# 08_CAN.net
KiCad netlist of a schematic drawn in Altium Designer
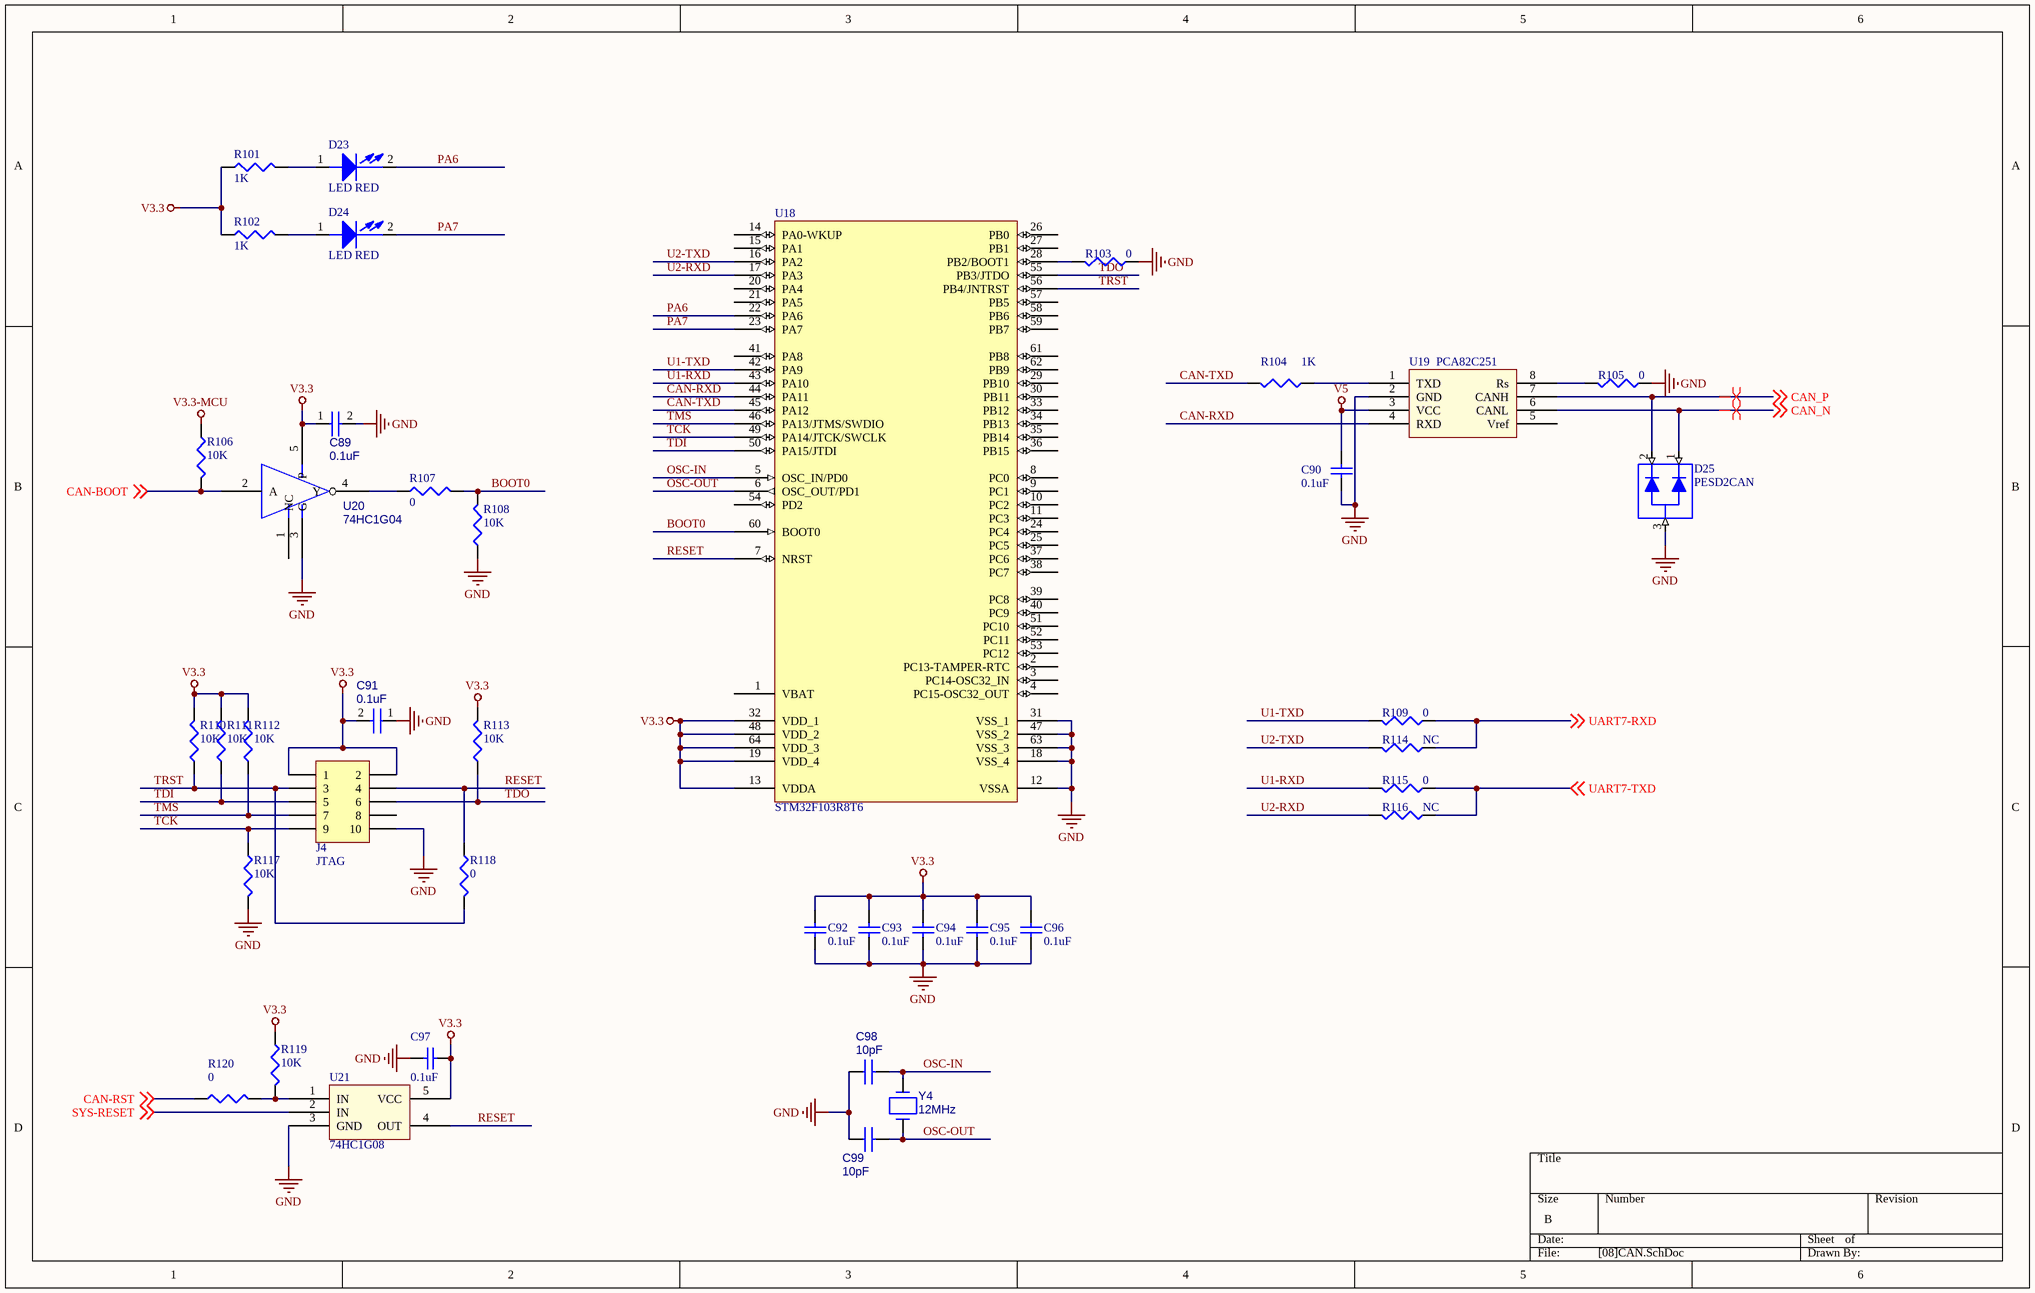
[diagram p0: [08]CAN.SchDoc]

(export (version "E")
  (design (tool "Eeschema 10.0.6"))
  (components
    (comp (ref "C89") (value "0.1uF") (footprint "0603") (libsource (lib "*") (part "CAP NP_Dup2")))
    (comp (ref "C90")
      (value "0.1uF")
      (footprint "0603")
      (description "Capacitor")
      (libsource (lib "Miscellaneous Devices") (part "Cap"))
    )
    (comp (ref "C91") (value "0.1uF") (libsource (lib "*") (part "CAP NP_Dup2")))
    (comp (ref "C92")
      (value "0.1uF")
      (footprint "0603")
      (description "Capacitor")
      (libsource (lib "Miscellaneous Devices") (part "Cap"))
    )
    (comp (ref "C93")
      (value "0.1uF")
      (footprint "0603")
      (description "Capacitor")
      (libsource (lib "Miscellaneous Devices") (part "Cap"))
    )
    (comp (ref "C94")
      (value "0.1uF")
      (footprint "0603")
      (description "Capacitor")
      (libsource (lib "Miscellaneous Devices") (part "Cap"))
    )
    (comp (ref "C95")
      (value "0.1uF")
      (footprint "0603")
      (description "Capacitor")
      (libsource (lib "Miscellaneous Devices") (part "Cap"))
    )
    (comp (ref "C96")
      (value "0.1uF")
      (footprint "0603")
      (description "Capacitor")
      (libsource (lib "Miscellaneous Devices") (part "Cap"))
    )
    (comp (ref "C97")
      (value "0.1uF")
      (footprint "0603")
      (description "Capacitor")
      (libsource (lib "Miscellaneous Devices") (part "Cap"))
    )
    (comp (ref "C98") (value "10pF") (libsource (lib "*") (part "CAP_Dup1")))
    (comp (ref "C99") (value "10pF") (libsource (lib "*") (part "CAP_Dup1")))
    (comp (ref "D23") (value "LED RED") (footprint "LED0603") (libsource (lib "*") (part "LN01401_1")))
    (comp (ref "D24") (value "LED RED") (footprint "LED0603") (libsource (lib "*") (part "LN01401_1")))
    (comp (ref "D25")
      (value "PESD2CAN")
      (footprint "PESD2CAN")
      (fields (field (name "PART NUMBER") "SCA00000J00"))
      (libsource (lib "Schlib") (part "PESD2CAN"))
    )
    (comp (ref "J4")
      (value "JTAG")
      (footprint "HDR2X5")
      (description "Header, 5-Pin, Dual row")
      (libsource (lib "Miscellaneous Connectors") (part "Header 5X2"))
    )
    (comp (ref "R101") (value "1K") (footprint "0603") (libsource (lib "*") (part "CR16-1003FM")))
    (comp (ref "R102") (value "1K") (footprint "0603") (libsource (lib "*") (part "CR16-1003FM")))
    (comp (ref "R103")
      (value "0")
      (footprint "0603")
      (description "Resistor")
      (libsource (lib "Miscellaneous Devices") (part "Res3"))
    )
    (comp (ref "R104")
      (value "1K")
      (footprint "0603")
      (description "Resistor")
      (libsource (lib "Miscellaneous Devices") (part "Res3"))
    )
    (comp (ref "R105")
      (value "0")
      (footprint "0603")
      (description "Resistor")
      (libsource (lib "Miscellaneous Devices") (part "Res3"))
    )
    (comp (ref "R106") (value "10K") (footprint "0603") (libsource (lib "*") (part "CR16-1003FM")))
    (comp (ref "R107")
      (value "0")
      (footprint "0603")
      (description "Resistor")
      (libsource (lib "Miscellaneous Devices") (part "Res3"))
    )
    (comp (ref "R108")
      (value "10K")
      (footprint "0603")
      (description "Resistor")
      (libsource (lib "Miscellaneous Devices") (part "Res3"))
    )
    (comp (ref "R109")
      (value "0")
      (footprint "0603")
      (description "Resistor")
      (libsource (lib "Miscellaneous Devices") (part "Res3"))
    )
    (comp (ref "R110")
      (value "10K")
      (footprint "0603")
      (description "Resistor")
      (libsource (lib "Miscellaneous Devices") (part "Res3"))
    )
    (comp (ref "R111")
      (value "10K")
      (footprint "0603")
      (description "Resistor")
      (libsource (lib "Miscellaneous Devices") (part "Res3"))
    )
    (comp (ref "R112")
      (value "10K")
      (footprint "0603")
      (description "Resistor")
      (libsource (lib "Miscellaneous Devices") (part "Res3"))
    )
    (comp (ref "R113")
      (value "10K")
      (footprint "0603")
      (description "Resistor")
      (libsource (lib "Miscellaneous Devices") (part "Res3"))
    )
    (comp (ref "R114")
      (value "NC")
      (footprint "0603")
      (description "Resistor")
      (libsource (lib "Miscellaneous Devices") (part "Res3"))
    )
    (comp (ref "R115")
      (value "0")
      (footprint "0603")
      (description "Resistor")
      (libsource (lib "Miscellaneous Devices") (part "Res3"))
    )
    (comp (ref "R116")
      (value "NC")
      (footprint "0603")
      (description "Resistor")
      (libsource (lib "Miscellaneous Devices") (part "Res3"))
    )
    (comp (ref "R117")
      (value "10K")
      (footprint "0603")
      (description "Resistor")
      (libsource (lib "Miscellaneous Devices") (part "Res3"))
    )
    (comp (ref "R118")
      (value "0")
      (footprint "0603")
      (description "Resistor")
      (libsource (lib "Miscellaneous Devices") (part "Res3"))
    )
    (comp (ref "R119")
      (value "10K")
      (footprint "0603")
      (description "Resistor")
      (libsource (lib "Miscellaneous Devices") (part "Res3"))
    )
    (comp (ref "R120")
      (value "0")
      (footprint "0603")
      (description "Resistor")
      (libsource (lib "Miscellaneous Devices") (part "Res3"))
    )
    (comp (ref "U18")
      (value "STM32F103R8T6")
      (footprint "LQFP64_N")
      (description "STM32 ARM-based 32-bit MCU with 64 Kbytes Flash, 64-pin LQFP, Industrial Temperature")
      (fields (field (name "PUBLISHER") "Altium Limited"))
      (libsource (lib "ST Microcontroller 32-Bit STM32") (part "STM32F103R8T6"))
    )
    (comp (ref "U19") (value "PCA82C251") (footprint "SO8") (libsource (lib "Schlib") (part "PCA82C251")))
    (comp (ref "U20") (value "74HC1G04") (libsource (lib "*") (part "74LVC1G04GW_SOT353-5")))
    (comp (ref "U21") (value "74HC1G08") (footprint "SOT23-5") (libsource (lib "Schlib") (part "74HC1G08")))
    (comp (ref "Y4") (value "12MHz") (libsource (lib "*") (part "CRYSTAL")))
  )
  (nets
    (net (code "1") (name "/BOOT0") (class "Default")
      (node (ref "R107") (pin "2") (pinfunction "2_2") (pintype "passive"))
      (node (ref "R108") (pin "2") (pinfunction "2_2") (pintype "passive"))
      (node (ref "U18") (pin "60") (pinfunction "BOOT0_60") (pintype "input"))
    )
    (net (code "2") (name "/CAN-RXD") (class "Default")
      (node (ref "U18") (pin "44") (pinfunction "PA11_44") (pintype "bidirectional"))
      (node (ref "U19") (pin "4") (pinfunction "RXD_4") (pintype "passive"))
    )
    (net (code "3") (name "/CAN-TXD") (class "Default")
      (node (ref "R104") (pin "2") (pinfunction "2_2") (pintype "passive"))
      (node (ref "U18") (pin "45") (pinfunction "PA12_45") (pintype "bidirectional"))
    )
    (net (code "4") (name "/OSC-IN") (class "Default")
      (node (ref "C98") (pin "2") (pinfunction "2_2") (pintype "passive"))
      (node (ref "U18") (pin "5") (pinfunction "OSC_IN/PD0_5") (pintype "input"))
      (node (ref "Y4") (pin "2") (pinfunction "2_2") (pintype "passive"))
    )
    (net (code "5") (name "/OSC-OUT") (class "Default")
      (node (ref "C99") (pin "2") (pinfunction "2_2") (pintype "passive"))
      (node (ref "U18") (pin "6") (pinfunction "OSC_OUT/PD1_6") (pintype "output"))
      (node (ref "Y4") (pin "1") (pinfunction "1_1") (pintype "passive"))
    )
    (net (code "6") (name "/PA6") (class "Default")
      (node (ref "D23") (pin "2") (pinfunction "CATHODE_2") (pintype "passive"))
      (node (ref "U18") (pin "22") (pinfunction "PA6_22") (pintype "bidirectional"))
    )
    (net (code "7") (name "/PA7") (class "Default")
      (node (ref "D24") (pin "2") (pinfunction "CATHODE_2") (pintype "passive"))
      (node (ref "U18") (pin "23") (pinfunction "PA7_23") (pintype "bidirectional"))
    )
    (net (code "8") (name "/RESET") (class "Default")
      (node (ref "J4") (pin "4") (pinfunction "4_4") (pintype "passive"))
      (node (ref "R118") (pin "1") (pinfunction "1_1") (pintype "passive"))
      (node (ref "U18") (pin "7") (pinfunction "NRST_7") (pintype "bidirectional"))
      (node (ref "U21") (pin "4") (pinfunction "OUT_4") (pintype "passive"))
    )
    (net (code "9") (name "/TCK") (class "Default")
      (node (ref "J4") (pin "9") (pinfunction "9_9") (pintype "passive"))
      (node (ref "R117") (pin "1") (pinfunction "1_1") (pintype "passive"))
      (node (ref "U18") (pin "49") (pinfunction "PA14/JTCK/SWCLK_49") (pintype "bidirectional"))
    )
    (net (code "10") (name "/TDI") (class "Default")
      (node (ref "J4") (pin "5") (pinfunction "5_5") (pintype "passive"))
      (node (ref "R111") (pin "1") (pinfunction "1_1") (pintype "passive"))
      (node (ref "U18") (pin "50") (pinfunction "PA15/JTDI_50") (pintype "bidirectional"))
    )
    (net (code "11") (name "/TDO") (class "Default")
      (node (ref "J4") (pin "6") (pinfunction "6_6") (pintype "passive"))
      (node (ref "R113") (pin "1") (pinfunction "1_1") (pintype "passive"))
      (node (ref "U18") (pin "55") (pinfunction "PB3/JTDO_55") (pintype "bidirectional"))
    )
    (net (code "12") (name "/TMS") (class "Default")
      (node (ref "J4") (pin "7") (pinfunction "7_7") (pintype "passive"))
      (node (ref "R112") (pin "1") (pinfunction "1_1") (pintype "passive"))
      (node (ref "U18") (pin "46") (pinfunction "PA13/JTMS/SWDIO_46") (pintype "bidirectional"))
    )
    (net (code "13") (name "/TRST") (class "Default")
      (node (ref "J4") (pin "3") (pinfunction "3_3") (pintype "passive"))
      (node (ref "R110") (pin "1") (pinfunction "1_1") (pintype "passive"))
      (node (ref "R118") (pin "2") (pinfunction "2_2") (pintype "passive"))
      (node (ref "U18") (pin "56") (pinfunction "PB4/JNTRST_56") (pintype "bidirectional"))
    )
    (net (code "14") (name "/U1-RXD") (class "Default")
      (node (ref "R115") (pin "2") (pinfunction "2_2") (pintype "passive"))
      (node (ref "U18") (pin "43") (pinfunction "PA10_43") (pintype "bidirectional"))
    )
    (net (code "15") (name "/U1-TXD") (class "Default")
      (node (ref "R109") (pin "2") (pinfunction "2_2") (pintype "passive"))
      (node (ref "U18") (pin "42") (pinfunction "PA9_42") (pintype "bidirectional"))
    )
    (net (code "16") (name "/U2-RXD") (class "Default")
      (node (ref "R116") (pin "2") (pinfunction "2_2") (pintype "passive"))
      (node (ref "U18") (pin "17") (pinfunction "PA3_17") (pintype "bidirectional"))
    )
    (net (code "17") (name "/U2-TXD") (class "Default")
      (node (ref "R114") (pin "2") (pinfunction "2_2") (pintype "passive"))
      (node (ref "U18") (pin "16") (pinfunction "PA2_16") (pintype "bidirectional"))
    )
    (net (code "18") (name "CAN-BOOT") (class "Default")
      (node (ref "R106") (pin "2") (pinfunction "2_2") (pintype "passive"))
      (node (ref "U20") (pin "2") (pinfunction "A_2") (pintype "passive"))
    )
    (net (code "19") (name "CAN-RST") (class "Default")
      (node (ref "R120") (pin "1") (pinfunction "1_1") (pintype "passive"))
    )
    (net (code "20") (name "CAN_N") (class "Default")
      (node (ref "D25") (pin "1") (pinfunction "1_1") (pintype "input"))
      (node (ref "U19") (pin "6") (pinfunction "CANL_6") (pintype "passive"))
    )
    (net (code "21") (name "CAN_P") (class "Default")
      (node (ref "D25") (pin "2") (pinfunction "2_2") (pintype "input"))
      (node (ref "U19") (pin "7") (pinfunction "CANH_7") (pintype "passive"))
    )
    (net (code "22") (name "GND") (class "Default")
      (node (ref "C89") (pin "2") (pinfunction "2_2") (pintype "passive"))
      (node (ref "C90") (pin "1") (pinfunction "1_1") (pintype "passive"))
      (node (ref "C91") (pin "1") (pinfunction "1_1") (pintype "passive"))
      (node (ref "C92") (pin "1") (pinfunction "1_1") (pintype "passive"))
      (node (ref "C93") (pin "1") (pinfunction "1_1") (pintype "passive"))
      (node (ref "C94") (pin "1") (pinfunction "1_1") (pintype "passive"))
      (node (ref "C95") (pin "1") (pinfunction "1_1") (pintype "passive"))
      (node (ref "C96") (pin "1") (pinfunction "1_1") (pintype "passive"))
      (node (ref "C97") (pin "2") (pinfunction "2_2") (pintype "passive"))
      (node (ref "C98") (pin "1") (pinfunction "1_1") (pintype "passive"))
      (node (ref "C99") (pin "1") (pinfunction "1_1") (pintype "passive"))
      (node (ref "D25") (pin "3") (pinfunction "3_3") (pintype "input"))
      (node (ref "J4") (pin "10") (pinfunction "10_10") (pintype "passive"))
      (node (ref "R103") (pin "1") (pinfunction "1_1") (pintype "passive"))
      (node (ref "R105") (pin "1") (pinfunction "1_1") (pintype "passive"))
      (node (ref "R108") (pin "1") (pinfunction "1_1") (pintype "passive"))
      (node (ref "R117") (pin "2") (pinfunction "2_2") (pintype "passive"))
      (node (ref "U18") (pin "12") (pinfunction "VSSA_12") (pintype "power_in"))
      (node (ref "U18") (pin "18") (pinfunction "VSS_4_18") (pintype "power_in"))
      (node (ref "U18") (pin "31") (pinfunction "VSS_1_31") (pintype "power_in"))
      (node (ref "U18") (pin "47") (pinfunction "VSS_2_47") (pintype "power_in"))
      (node (ref "U18") (pin "63") (pinfunction "VSS_3_63") (pintype "power_in"))
      (node (ref "U19") (pin "2") (pinfunction "GND_2") (pintype "passive"))
      (node (ref "U20") (pin "3") (pinfunction "G_3") (pintype "passive"))
      (node (ref "U21") (pin "3") (pinfunction "GND_3") (pintype "passive"))
    )
    (net (code "23") (name "Net-(D23-ANODE)") (class "Default")
      (node (ref "D23") (pin "1") (pinfunction "ANODE_1") (pintype "passive"))
      (node (ref "R101") (pin "2") (pinfunction "2_2") (pintype "passive"))
    )
    (net (code "24") (name "Net-(D24-ANODE)") (class "Default")
      (node (ref "D24") (pin "1") (pinfunction "ANODE_1") (pintype "passive"))
      (node (ref "R102") (pin "2") (pinfunction "2_2") (pintype "passive"))
    )
    (net (code "25") (name "Net-(R119-Pad2)") (class "Default")
      (node (ref "R119") (pin "2") (pinfunction "2_2") (pintype "passive"))
      (node (ref "R120") (pin "2") (pinfunction "2_2") (pintype "passive"))
      (node (ref "U21") (pin "1") (pinfunction "IN_1") (pintype "passive"))
    )
    (net (code "26") (name "Net-(U18-PB2{slash}BOOT1)") (class "Default")
      (node (ref "R103") (pin "2") (pinfunction "2_2") (pintype "passive"))
      (node (ref "U18") (pin "28") (pinfunction "PB2/BOOT1_28") (pintype "bidirectional"))
    )
    (net (code "27") (name "Net-(U19-Rs)") (class "Default")
      (node (ref "R105") (pin "2") (pinfunction "2_2") (pintype "passive"))
      (node (ref "U19") (pin "8") (pinfunction "Rs_8") (pintype "passive"))
    )
    (net (code "28") (name "Net-(U19-TXD)") (class "Default")
      (node (ref "R104") (pin "1") (pinfunction "1_1") (pintype "passive"))
      (node (ref "U19") (pin "1") (pinfunction "TXD_1") (pintype "passive"))
    )
    (net (code "29") (name "Net-(U20-Y)") (class "Default")
      (node (ref "R107") (pin "1") (pinfunction "1_1") (pintype "passive"))
      (node (ref "U20") (pin "4") (pinfunction "Y_4") (pintype "passive"))
    )
    (net (code "30") (name "SYS-RESET") (class "Default")
      (node (ref "U21") (pin "2") (pinfunction "IN_2") (pintype "passive"))
    )
    (net (code "31") (name "UART7-RXD") (class "Default")
      (node (ref "R109") (pin "1") (pinfunction "1_1") (pintype "passive"))
      (node (ref "R114") (pin "1") (pinfunction "1_1") (pintype "passive"))
    )
    (net (code "32") (name "UART7-TXD") (class "Default")
      (node (ref "R115") (pin "1") (pinfunction "1_1") (pintype "passive"))
      (node (ref "R116") (pin "1") (pinfunction "1_1") (pintype "passive"))
    )
    (net (code "33") (name "V3.3") (class "Default")
      (node (ref "C89") (pin "1") (pinfunction "1_1") (pintype "passive"))
      (node (ref "C91") (pin "2") (pinfunction "2_2") (pintype "passive"))
      (node (ref "C92") (pin "2") (pinfunction "2_2") (pintype "passive"))
      (node (ref "C93") (pin "2") (pinfunction "2_2") (pintype "passive"))
      (node (ref "C94") (pin "2") (pinfunction "2_2") (pintype "passive"))
      (node (ref "C95") (pin "2") (pinfunction "2_2") (pintype "passive"))
      (node (ref "C96") (pin "2") (pinfunction "2_2") (pintype "passive"))
      (node (ref "C97") (pin "1") (pinfunction "1_1") (pintype "passive"))
      (node (ref "J4") (pin "1") (pinfunction "1_1") (pintype "passive"))
      (node (ref "J4") (pin "2") (pinfunction "2_2") (pintype "passive"))
      (node (ref "R101") (pin "1") (pinfunction "1_1") (pintype "passive"))
      (node (ref "R102") (pin "1") (pinfunction "1_1") (pintype "passive"))
      (node (ref "R110") (pin "2") (pinfunction "2_2") (pintype "passive"))
      (node (ref "R111") (pin "2") (pinfunction "2_2") (pintype "passive"))
      (node (ref "R112") (pin "2") (pinfunction "2_2") (pintype "passive"))
      (node (ref "R113") (pin "2") (pinfunction "2_2") (pintype "passive"))
      (node (ref "R119") (pin "1") (pinfunction "1_1") (pintype "passive"))
      (node (ref "U18") (pin "13") (pinfunction "VDDA_13") (pintype "power_in"))
      (node (ref "U18") (pin "19") (pinfunction "VDD_4_19") (pintype "power_in"))
      (node (ref "U18") (pin "32") (pinfunction "VDD_1_32") (pintype "power_in"))
      (node (ref "U18") (pin "48") (pinfunction "VDD_2_48") (pintype "power_in"))
      (node (ref "U18") (pin "64") (pinfunction "VDD_3_64") (pintype "power_in"))
      (node (ref "U20") (pin "5") (pinfunction "P_5") (pintype "passive"))
      (node (ref "U21") (pin "5") (pinfunction "VCC_5") (pintype "passive"))
    )
    (net (code "34") (name "V3.3-MCU") (class "Default")
      (node (ref "R106") (pin "1") (pinfunction "1_1") (pintype "passive"))
    )
    (net (code "35") (name "V5") (class "Default")
      (node (ref "C90") (pin "2") (pinfunction "2_2") (pintype "passive"))
      (node (ref "U19") (pin "3") (pinfunction "VCC_3") (pintype "passive"))
    )
    (net (code "36") (name "unconnected-(J4-Pad8)") (class "Default")
      (node (ref "J4") (pin "8") (pinfunction "8_8") (pintype "passive"))
    )
    (net (code "37") (name "unconnected-(U18-PA0-WKUP-Pad14)") (class "Default")
      (node (ref "U18") (pin "14") (pinfunction "PA0-WKUP_14") (pintype "bidirectional"))
    )
    (net (code "38") (name "unconnected-(U18-PA1-Pad15)") (class "Default")
      (node (ref "U18") (pin "15") (pinfunction "PA1_15") (pintype "bidirectional"))
    )
    (net (code "39") (name "unconnected-(U18-PA4-Pad20)") (class "Default")
      (node (ref "U18") (pin "20") (pinfunction "PA4_20") (pintype "bidirectional"))
    )
    (net (code "40") (name "unconnected-(U18-PA5-Pad21)") (class "Default")
      (node (ref "U18") (pin "21") (pinfunction "PA5_21") (pintype "bidirectional"))
    )
    (net (code "41") (name "unconnected-(U18-PA8-Pad41)") (class "Default")
      (node (ref "U18") (pin "41") (pinfunction "PA8_41") (pintype "bidirectional"))
    )
    (net (code "42") (name "unconnected-(U18-PB0-Pad26)") (class "Default")
      (node (ref "U18") (pin "26") (pinfunction "PB0_26") (pintype "bidirectional"))
    )
    (net (code "43") (name "unconnected-(U18-PB1-Pad27)") (class "Default")
      (node (ref "U18") (pin "27") (pinfunction "PB1_27") (pintype "bidirectional"))
    )
    (net (code "44") (name "unconnected-(U18-PB5-Pad57)") (class "Default")
      (node (ref "U18") (pin "57") (pinfunction "PB5_57") (pintype "bidirectional"))
    )
    (net (code "45") (name "unconnected-(U18-PB6-Pad58)") (class "Default")
      (node (ref "U18") (pin "58") (pinfunction "PB6_58") (pintype "bidirectional"))
    )
    (net (code "46") (name "unconnected-(U18-PB7-Pad59)") (class "Default")
      (node (ref "U18") (pin "59") (pinfunction "PB7_59") (pintype "bidirectional"))
    )
    (net (code "47") (name "unconnected-(U18-PB8-Pad61)") (class "Default")
      (node (ref "U18") (pin "61") (pinfunction "PB8_61") (pintype "bidirectional"))
    )
    (net (code "48") (name "unconnected-(U18-PB9-Pad62)") (class "Default")
      (node (ref "U18") (pin "62") (pinfunction "PB9_62") (pintype "bidirectional"))
    )
    (net (code "49") (name "unconnected-(U18-PB10-Pad29)") (class "Default")
      (node (ref "U18") (pin "29") (pinfunction "PB10_29") (pintype "bidirectional"))
    )
    (net (code "50") (name "unconnected-(U18-PB11-Pad30)") (class "Default")
      (node (ref "U18") (pin "30") (pinfunction "PB11_30") (pintype "bidirectional"))
    )
    (net (code "51") (name "unconnected-(U18-PB12-Pad33)") (class "Default")
      (node (ref "U18") (pin "33") (pinfunction "PB12_33") (pintype "bidirectional"))
    )
    (net (code "52") (name "unconnected-(U18-PB13-Pad34)") (class "Default")
      (node (ref "U18") (pin "34") (pinfunction "PB13_34") (pintype "bidirectional"))
    )
    (net (code "53") (name "unconnected-(U18-PB14-Pad35)") (class "Default")
      (node (ref "U18") (pin "35") (pinfunction "PB14_35") (pintype "bidirectional"))
    )
    (net (code "54") (name "unconnected-(U18-PB15-Pad36)") (class "Default")
      (node (ref "U18") (pin "36") (pinfunction "PB15_36") (pintype "bidirectional"))
    )
    (net (code "55") (name "unconnected-(U18-PC0-Pad8)") (class "Default")
      (node (ref "U18") (pin "8") (pinfunction "PC0_8") (pintype "bidirectional"))
    )
    (net (code "56") (name "unconnected-(U18-PC1-Pad9)") (class "Default")
      (node (ref "U18") (pin "9") (pinfunction "PC1_9") (pintype "bidirectional"))
    )
    (net (code "57") (name "unconnected-(U18-PC2-Pad10)") (class "Default")
      (node (ref "U18") (pin "10") (pinfunction "PC2_10") (pintype "bidirectional"))
    )
    (net (code "58") (name "unconnected-(U18-PC3-Pad11)") (class "Default")
      (node (ref "U18") (pin "11") (pinfunction "PC3_11") (pintype "bidirectional"))
    )
    (net (code "59") (name "unconnected-(U18-PC4-Pad24)") (class "Default")
      (node (ref "U18") (pin "24") (pinfunction "PC4_24") (pintype "bidirectional"))
    )
    (net (code "60") (name "unconnected-(U18-PC5-Pad25)") (class "Default")
      (node (ref "U18") (pin "25") (pinfunction "PC5_25") (pintype "bidirectional"))
    )
    (net (code "61") (name "unconnected-(U18-PC6-Pad37)") (class "Default")
      (node (ref "U18") (pin "37") (pinfunction "PC6_37") (pintype "bidirectional"))
    )
    (net (code "62") (name "unconnected-(U18-PC7-Pad38)") (class "Default")
      (node (ref "U18") (pin "38") (pinfunction "PC7_38") (pintype "bidirectional"))
    )
    (net (code "63") (name "unconnected-(U18-PC8-Pad39)") (class "Default")
      (node (ref "U18") (pin "39") (pinfunction "PC8_39") (pintype "bidirectional"))
    )
    (net (code "64") (name "unconnected-(U18-PC9-Pad40)") (class "Default")
      (node (ref "U18") (pin "40") (pinfunction "PC9_40") (pintype "bidirectional"))
    )
    (net (code "65") (name "unconnected-(U18-PC10-Pad51)") (class "Default")
      (node (ref "U18") (pin "51") (pinfunction "PC10_51") (pintype "bidirectional"))
    )
    (net (code "66") (name "unconnected-(U18-PC11-Pad52)") (class "Default")
      (node (ref "U18") (pin "52") (pinfunction "PC11_52") (pintype "bidirectional"))
    )
    (net (code "67") (name "unconnected-(U18-PC12-Pad53)") (class "Default")
      (node (ref "U18") (pin "53") (pinfunction "PC12_53") (pintype "bidirectional"))
    )
    (net (code "68") (name "unconnected-(U18-PC13-TAMPER-RTC-Pad2)") (class "Default")
      (node (ref "U18") (pin "2") (pinfunction "PC13-TAMPER-RTC_2") (pintype "bidirectional"))
    )
    (net (code "69") (name "unconnected-(U18-PC14-OSC32_IN-Pad3)") (class "Default")
      (node (ref "U18") (pin "3") (pinfunction "PC14-OSC32_IN_3") (pintype "bidirectional"))
    )
    (net (code "70") (name "unconnected-(U18-PC15-OSC32_OUT-Pad4)") (class "Default")
      (node (ref "U18") (pin "4") (pinfunction "PC15-OSC32_OUT_4") (pintype "bidirectional"))
    )
    (net (code "71") (name "unconnected-(U18-PD2-Pad54)") (class "Default")
      (node (ref "U18") (pin "54") (pinfunction "PD2_54") (pintype "bidirectional"))
    )
    (net (code "72") (name "unconnected-(U18-VBAT-Pad1)") (class "Default")
      (node (ref "U18") (pin "1") (pinfunction "VBAT_1") (pintype "power_in"))
    )
    (net (code "73") (name "unconnected-(U19-Vref-Pad5)") (class "Default")
      (node (ref "U19") (pin "5") (pinfunction "Vref_5") (pintype "passive"))
    )
    (net (code "74") (name "unconnected-(U20-NC-Pad1)") (class "Default")
      (node (ref "U20") (pin "1") (pinfunction "NC_1") (pintype "passive"))
    )
  )
)
